# ProProject_Access_Control_Signal_Relay_S.net
KiCad netlist of a schematic drawn in EasyEDA Pro
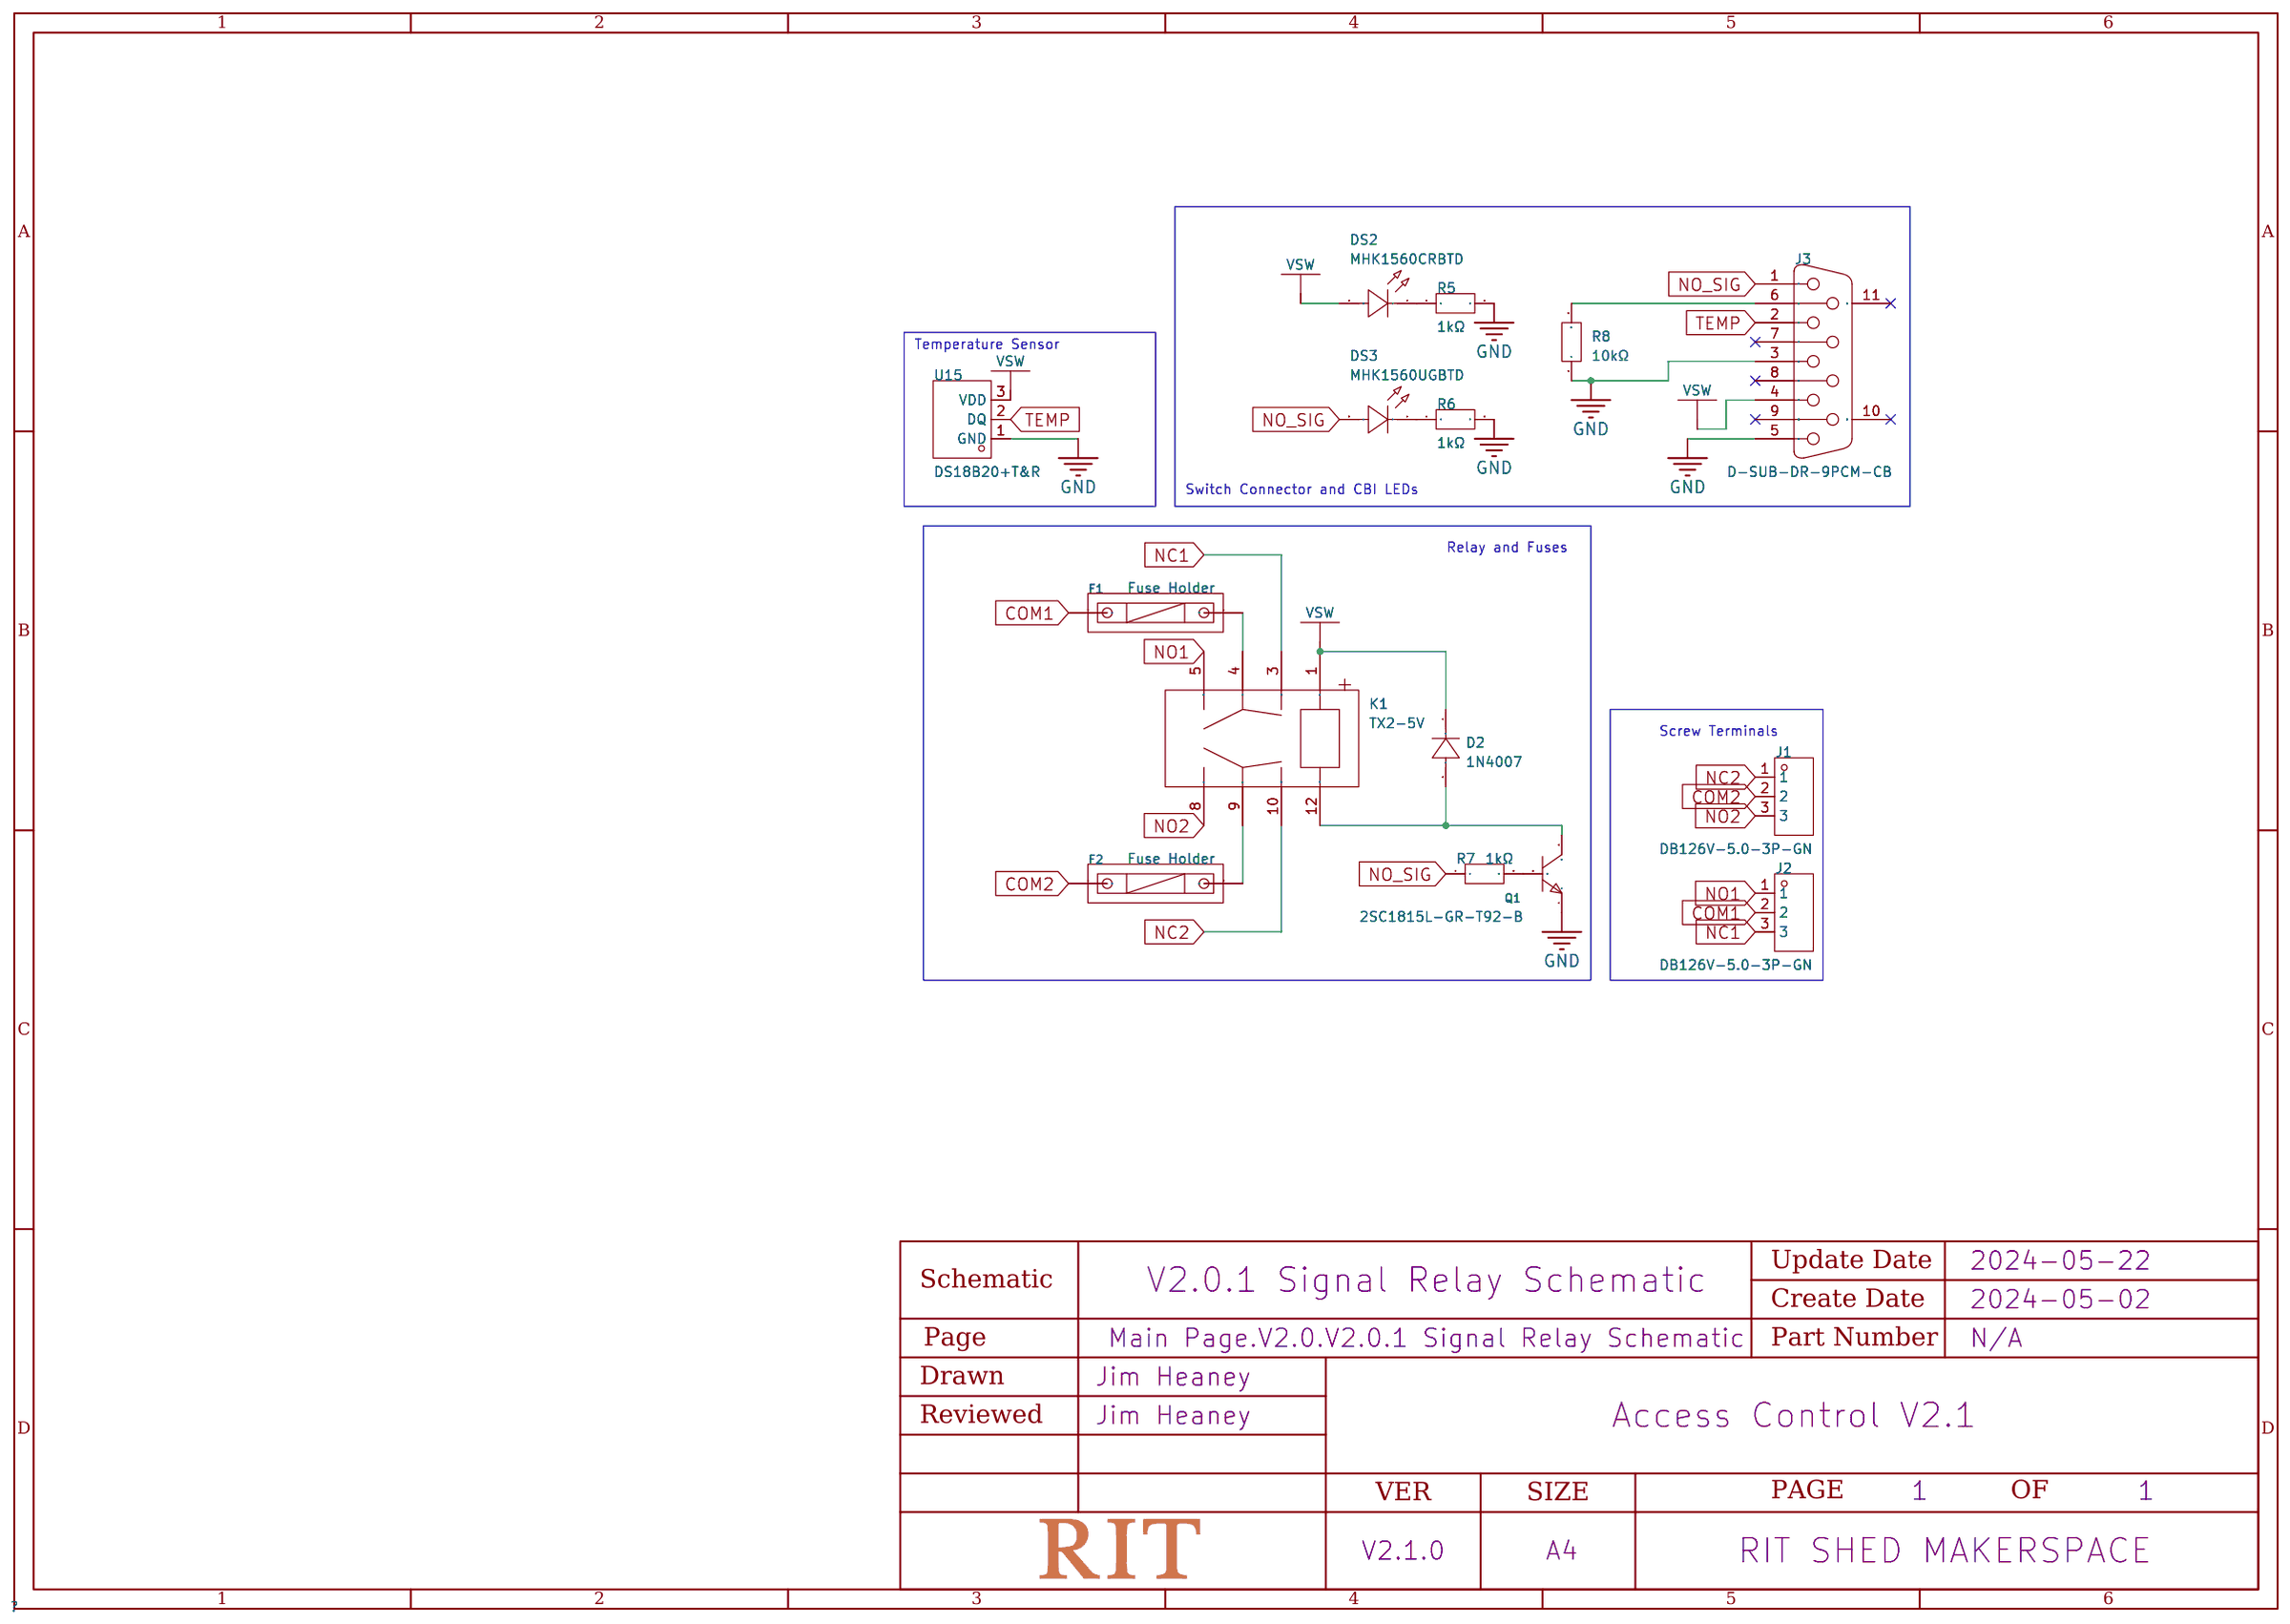
[diagram p0: schematic sheet]

(export (version "E")
  (design (tool "Eeschema 10.0.6"))
  (components
    (comp (ref "D2")
      (value "1N4007")
      (footprint "easyedapro:DO-41_BD2.4-L4.7-P8.70-D0.8-RD")
      (fields (field (name "Manufacturer") "GOODWORK(固得沃克)"))
      (libsource (lib "easyedapro") (part "1N4007_C2985028"))
    )
    (comp (ref "DS2")
      (value "MHK1560CRBTD")
      (footprint "easyedapro:LED-TH_MHK1560UGBTD")
      (fields (field (name "Manufacturer") "MEIHUA(美华)"))
      (libsource (lib "easyedapro") (part "MHK1560CGBTD"))
    )
    (comp (ref "DS3")
      (value "MHK1560UGBTD")
      (footprint "easyedapro:LED-TH_MHK1560UGBTD")
      (fields (field (name "Manufacturer") "MEIHUA(美华)"))
      (libsource (lib "easyedapro") (part "MHK1560UGBTD"))
    )
    (comp (ref "F1")
      (value "Fuse Holder")
      (footprint "easyedapro:FUSE-TH_L24.5-W9.8-P22.5")
      (description "Fuseholder Type:- Fuse Type:- Fuse Size:-")
      (fields (field (name "Manufacturer Part") "保险丝透明座") (field (name "Manufacturer") "xcfuse(旭程)"))
      (libsource (lib "easyedapro") (part "Fuse transparent seat"))
    )
    (comp (ref "F2")
      (value "Fuse Holder")
      (footprint "easyedapro:FUSE-TH_L24.5-W9.8-P22.5")
      (description "Fuseholder Type:- Fuse Type:- Fuse Size:-")
      (fields (field (name "Manufacturer Part") "保险丝透明座") (field (name "Manufacturer") "xcfuse(旭程)"))
      (libsource (lib "easyedapro") (part "Fuse transparent seat"))
    )
    (comp (ref "J1")
      (value "DB126V-5.0-3P-GN")
      (footprint "easyedapro:CONN-TH_3P-P5.00_DB126V-5.0-3P")
      (fields (field (name "Manufacturer") "DORABO(地博电气)"))
      (libsource (lib "easyedapro") (part "DB126V-5.0-3P"))
    )
    (comp (ref "J2")
      (value "DB126V-5.0-3P-GN")
      (footprint "easyedapro:CONN-TH_3P-P5.00_DB126V-5.0-3P")
      (fields (field (name "Manufacturer") "DORABO(地博电气)"))
      (libsource (lib "easyedapro") (part "DB126V-5.0-3P"))
    )
    (comp (ref "J3")
      (value "D-SUB-DR-9PCM-CB")
      (footprint "easyedapro:DB9-TH_ID09S33E4GV00LF")
      (fields (field (name "Manufacturer") "XUNPU(讯普)"))
      (libsource (lib "easyedapro") (part "D-SUB-DR-9PCM-CB"))
    )
    (comp (ref "K1")
      (value "TX2-5V")
      (footprint "easyedapro:RELAY-TH_TX2-3V")
      (fields (field (name "Manufacturer") "PANASONIC(松下)"))
      (libsource (lib "easyedapro") (part "TX2-5V"))
    )
    (comp (ref "Q1")
      (value "2SC1815L-GR-T92-B")
      (footprint "easyedapro:TO-92-3_L4.9-W3.7-P2.54-L")
      (fields (field (name "Manufacturer") "UTC(友顺)"))
      (libsource (lib "easyedapro") (part "2SC1815L-GR-T92-B"))
    )
    (comp (ref "R5")
      (value "1kΩ")
      (footprint "easyedapro:RES-TH_BD2.3-L6.5-P10.50-D0.5")
      (fields (field (name "Manufacturer Part") "MF1/4W-1KΩ±1%T52") (field (name "Manufacturer") "华星机电"))
      (libsource (lib "easyedapro") (part "MF1/4W-1KΩ±1%T52"))
    )
    (comp (ref "R6")
      (value "1kΩ")
      (footprint "easyedapro:RES-TH_BD2.3-L6.5-P10.50-D0.5")
      (fields (field (name "Manufacturer Part") "MF1/4W-1KΩ±1%T52") (field (name "Manufacturer") "华星机电"))
      (libsource (lib "easyedapro") (part "MF1/4W-1KΩ±1%T52"))
    )
    (comp (ref "R7")
      (value "1kΩ")
      (footprint "easyedapro:RES-TH_BD2.3-L6.5-P10.50-D0.5")
      (fields (field (name "Manufacturer Part") "MF1/4W-1KΩ±1%T52") (field (name "Manufacturer") "华星机电"))
      (libsource (lib "easyedapro") (part "MF1/4W-1KΩ±1%T52"))
    )
    (comp (ref "R8")
      (value "10kΩ")
      (footprint "easyedapro:RES-TH_BD2.7-L6.2-P10.20-D0.4")
      (fields (field (name "Manufacturer Part") "CR1/4W-10K±5%-ST26") (field (name "Manufacturer") "VO(翔胜)"))
      (libsource (lib "easyedapro") (part "CR1/4W-10K±5%-ST26"))
    )
    (comp (ref "U15")
      (value "DS18B20+T&R")
      (footprint "easyedapro:TO-92-3_L4.9-W3.7-P2.54-L")
      (description "Supply Voltage:3V~5.5V Supply Voltage:3V~5.5V")
      (fields (field (name "Manufacturer") "ADI(亚德诺)/MAXIM(美信)"))
      (libsource (lib "easyedapro") (part "DS18B20+T&R"))
    )
  )
  (nets
    (net (code "1") (name "COM1") (class "Default")
      (node (ref "F1") (pin "1") (pinfunction "1_1") (pintype "input"))
      (node (ref "J2") (pin "2") (pinfunction "2_2") (pintype "unspecified"))
    )
    (net (code "2") (name "COM2") (class "Default")
      (node (ref "F2") (pin "1") (pinfunction "1_1") (pintype "input"))
      (node (ref "J1") (pin "2") (pinfunction "2_2") (pintype "unspecified"))
    )
    (net (code "3") (name "GND") (class "Default")
      (node (ref "J3") (pin "3") (pinfunction "3_3") (pintype "input"))
      (node (ref "J3") (pin "5") (pinfunction "5_5") (pintype "input"))
      (node (ref "Q1") (pin "1") (pinfunction "E_1") (pintype "input"))
      (node (ref "R5") (pin "2") (pinfunction "2_2") (pintype "unspecified"))
      (node (ref "R6") (pin "2") (pinfunction "2_2") (pintype "unspecified"))
      (node (ref "R8") (pin "1") (pinfunction "1_1") (pintype "unspecified"))
      (node (ref "U15") (pin "1") (pinfunction "GND_1") (pintype "unspecified"))
    )
    (net (code "4") (name "NC1") (class "Default")
      (node (ref "J2") (pin "3") (pinfunction "3_3") (pintype "unspecified"))
      (node (ref "K1") (pin "3") (pinfunction "3_3") (pintype "input"))
    )
    (net (code "5") (name "NC2") (class "Default")
      (node (ref "J1") (pin "1") (pinfunction "1_1") (pintype "unspecified"))
      (node (ref "K1") (pin "10") (pinfunction "10_10") (pintype "input"))
    )
    (net (code "6") (name "NO1") (class "Default")
      (node (ref "J2") (pin "1") (pinfunction "1_1") (pintype "unspecified"))
      (node (ref "K1") (pin "5") (pinfunction "5_5") (pintype "input"))
    )
    (net (code "7") (name "NO2") (class "Default")
      (node (ref "J1") (pin "3") (pinfunction "3_3") (pintype "unspecified"))
      (node (ref "K1") (pin "8") (pinfunction "8_8") (pintype "input"))
    )
    (net (code "8") (name "NO_SIG") (class "Default")
      (node (ref "DS3") (pin "2") (pinfunction "A_2") (pintype "unspecified"))
      (node (ref "J3") (pin "1") (pinfunction "1_1") (pintype "input"))
      (node (ref "R7") (pin "1") (pinfunction "1_1") (pintype "unspecified"))
    )
    (net (code "9") (name "Net-(D2-A)") (class "Default")
      (node (ref "D2") (pin "2") (pinfunction "A_2") (pintype "unspecified"))
      (node (ref "K1") (pin "12") (pinfunction "12_12") (pintype "input"))
      (node (ref "Q1") (pin "2") (pinfunction "C_2") (pintype "input"))
    )
    (net (code "10") (name "Net-(DS2-K)") (class "Default")
      (node (ref "DS2") (pin "1") (pinfunction "K_1") (pintype "unspecified"))
      (node (ref "R5") (pin "1") (pinfunction "1_1") (pintype "unspecified"))
    )
    (net (code "11") (name "Net-(DS3-K)") (class "Default")
      (node (ref "DS3") (pin "1") (pinfunction "K_1") (pintype "unspecified"))
      (node (ref "R6") (pin "1") (pinfunction "1_1") (pintype "unspecified"))
    )
    (net (code "12") (name "Net-(F1-Pad2)") (class "Default")
      (node (ref "F1") (pin "2") (pinfunction "2_2") (pintype "input"))
      (node (ref "K1") (pin "4") (pinfunction "4_4") (pintype "input"))
    )
    (net (code "13") (name "Net-(F2-Pad2)") (class "Default")
      (node (ref "F2") (pin "2") (pinfunction "2_2") (pintype "input"))
      (node (ref "K1") (pin "9") (pinfunction "9_9") (pintype "input"))
    )
    (net (code "14") (name "Net-(J3-Pad6)") (class "Default")
      (node (ref "J3") (pin "6") (pinfunction "6_6") (pintype "input"))
      (node (ref "R8") (pin "2") (pinfunction "2_2") (pintype "unspecified"))
    )
    (net (code "15") (name "Net-(Q1-B)") (class "Default")
      (node (ref "Q1") (pin "3") (pinfunction "B_3") (pintype "input"))
      (node (ref "R7") (pin "2") (pinfunction "2_2") (pintype "unspecified"))
    )
    (net (code "16") (name "TEMP") (class "Default")
      (node (ref "J3") (pin "2") (pinfunction "2_2") (pintype "input"))
      (node (ref "U15") (pin "2") (pinfunction "DQ_2") (pintype "unspecified"))
    )
    (net (code "17") (name "VSW") (class "Default")
      (node (ref "D2") (pin "1") (pinfunction "K_1") (pintype "unspecified"))
      (node (ref "DS2") (pin "2") (pinfunction "A_2") (pintype "unspecified"))
      (node (ref "J3") (pin "4") (pinfunction "4_4") (pintype "input"))
      (node (ref "K1") (pin "1") (pinfunction "1_1") (pintype "input"))
      (node (ref "U15") (pin "3") (pinfunction "VDD_3") (pintype "unspecified"))
    )
    (net (code "18") (name "unconnected-(J3-MH1-Pad10)") (class "Default")
      (node (ref "J3") (pin "10") (pinfunction "MH1_10") (pintype "input+no_connect"))
    )
    (net (code "19") (name "unconnected-(J3-MH2-Pad11)") (class "Default")
      (node (ref "J3") (pin "11") (pinfunction "MH2_11") (pintype "input+no_connect"))
    )
    (net (code "20") (name "unconnected-(J3-Pad7)") (class "Default")
      (node (ref "J3") (pin "7") (pinfunction "7_7") (pintype "input+no_connect"))
    )
    (net (code "21") (name "unconnected-(J3-Pad8)") (class "Default")
      (node (ref "J3") (pin "8") (pinfunction "8_8") (pintype "input+no_connect"))
    )
    (net (code "22") (name "unconnected-(J3-Pad9)") (class "Default")
      (node (ref "J3") (pin "9") (pinfunction "9_9") (pintype "input+no_connect"))
    )
  )
)
